# OpenOTA.net
KiCad netlist of a schematic drawn in EAGLE
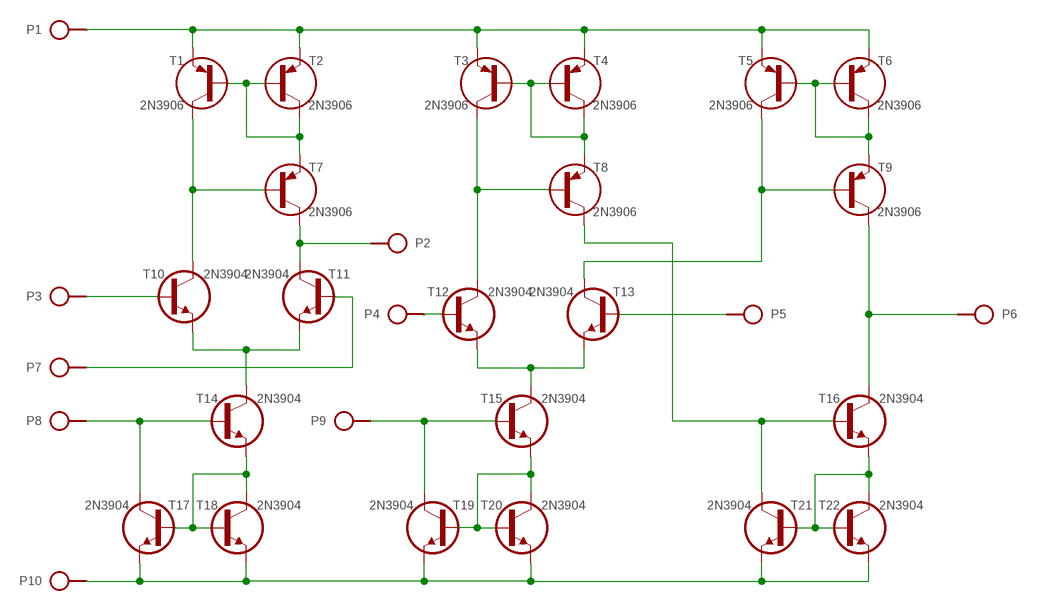
[diagram p0: schematic, sheet 1]

(export (version "E")
  (design (tool "Eeschema 10.0.6"))
  (components
    (comp (ref "P1")
      (value "SPAD")
      (footprint "eagle-import:SPAD")
      (libsource (lib "eagle-import") (part "SPAD"))
    )
    (comp (ref "P2")
      (value "SPAD")
      (footprint "eagle-import:SPAD")
      (libsource (lib "eagle-import") (part "SPAD"))
    )
    (comp (ref "P3")
      (value "SPAD")
      (footprint "eagle-import:SPAD")
      (libsource (lib "eagle-import") (part "SPAD"))
    )
    (comp (ref "P4")
      (value "SPAD")
      (footprint "eagle-import:SPAD")
      (libsource (lib "eagle-import") (part "SPAD"))
    )
    (comp (ref "P5")
      (value "SPAD")
      (footprint "eagle-import:SPAD")
      (libsource (lib "eagle-import") (part "SPAD"))
    )
    (comp (ref "P6")
      (value "SPAD")
      (footprint "eagle-import:SPAD")
      (libsource (lib "eagle-import") (part "SPAD"))
    )
    (comp (ref "P7")
      (value "SPAD")
      (footprint "eagle-import:SPAD")
      (libsource (lib "eagle-import") (part "SPAD"))
    )
    (comp (ref "P8")
      (value "SPAD")
      (footprint "eagle-import:SPAD")
      (libsource (lib "eagle-import") (part "SPAD"))
    )
    (comp (ref "P9")
      (value "SPAD")
      (footprint "eagle-import:SPAD")
      (libsource (lib "eagle-import") (part "SPAD"))
    )
    (comp (ref "P10")
      (value "SPAD")
      (footprint "eagle-import:SPAD")
      (libsource (lib "eagle-import") (part "SPAD"))
    )
    (comp (ref "T1")
      (value "2N3906")
      (footprint "eagle-import:TO92")
      (libsource (lib "eagle-import") (part "2N3906"))
    )
    (comp (ref "T2")
      (value "2N3906")
      (footprint "eagle-import:TO92")
      (libsource (lib "eagle-import") (part "2N3906"))
    )
    (comp (ref "T3")
      (value "2N3906")
      (footprint "eagle-import:TO92")
      (libsource (lib "eagle-import") (part "2N3906"))
    )
    (comp (ref "T4")
      (value "2N3906")
      (footprint "eagle-import:TO92")
      (libsource (lib "eagle-import") (part "2N3906"))
    )
    (comp (ref "T5")
      (value "2N3906")
      (footprint "eagle-import:TO92")
      (libsource (lib "eagle-import") (part "2N3906"))
    )
    (comp (ref "T6")
      (value "2N3906")
      (footprint "eagle-import:TO92")
      (libsource (lib "eagle-import") (part "2N3906"))
    )
    (comp (ref "T7")
      (value "2N3906")
      (footprint "eagle-import:TO92")
      (libsource (lib "eagle-import") (part "2N3906"))
    )
    (comp (ref "T8")
      (value "2N3906")
      (footprint "eagle-import:TO92")
      (libsource (lib "eagle-import") (part "2N3906"))
    )
    (comp (ref "T9")
      (value "2N3906")
      (footprint "eagle-import:TO92")
      (libsource (lib "eagle-import") (part "2N3906"))
    )
    (comp (ref "T10")
      (value "2N3904")
      (footprint "eagle-import:TO92")
      (libsource (lib "eagle-import") (part "2N3904"))
    )
    (comp (ref "T11")
      (value "2N3904")
      (footprint "eagle-import:TO92")
      (libsource (lib "eagle-import") (part "2N3904"))
    )
    (comp (ref "T12")
      (value "2N3904")
      (footprint "eagle-import:TO92")
      (libsource (lib "eagle-import") (part "2N3904"))
    )
    (comp (ref "T13")
      (value "2N3904")
      (footprint "eagle-import:TO92")
      (libsource (lib "eagle-import") (part "2N3904"))
    )
    (comp (ref "T14")
      (value "2N3904")
      (footprint "eagle-import:TO92")
      (libsource (lib "eagle-import") (part "2N3904"))
    )
    (comp (ref "T15")
      (value "2N3904")
      (footprint "eagle-import:TO92")
      (libsource (lib "eagle-import") (part "2N3904"))
    )
    (comp (ref "T16")
      (value "2N3904")
      (footprint "eagle-import:TO92")
      (libsource (lib "eagle-import") (part "2N3904"))
    )
    (comp (ref "T17")
      (value "2N3904")
      (footprint "eagle-import:TO92")
      (libsource (lib "eagle-import") (part "2N3904"))
    )
    (comp (ref "T18")
      (value "2N3904")
      (footprint "eagle-import:TO92")
      (libsource (lib "eagle-import") (part "2N3904"))
    )
    (comp (ref "T19")
      (value "2N3904")
      (footprint "eagle-import:TO92")
      (libsource (lib "eagle-import") (part "2N3904"))
    )
    (comp (ref "T20")
      (value "2N3904")
      (footprint "eagle-import:TO92")
      (libsource (lib "eagle-import") (part "2N3904"))
    )
    (comp (ref "T21")
      (value "2N3904")
      (footprint "eagle-import:TO92")
      (libsource (lib "eagle-import") (part "2N3904"))
    )
    (comp (ref "T22")
      (value "2N3904")
      (footprint "eagle-import:TO92")
      (libsource (lib "eagle-import") (part "2N3904"))
    )
  )
  (nets
    (net (code "1") (name "Net-(P1-P$1)") (class "Default")
      (node (ref "P1") (pin "1") (pinfunction "P$1_1") (pintype "passive"))
      (node (ref "T1") (pin "1") (pinfunction "E_1") (pintype "passive"))
      (node (ref "T2") (pin "1") (pinfunction "E_1") (pintype "passive"))
      (node (ref "T3") (pin "1") (pinfunction "E_1") (pintype "passive"))
      (node (ref "T4") (pin "1") (pinfunction "E_1") (pintype "passive"))
      (node (ref "T5") (pin "1") (pinfunction "E_1") (pintype "passive"))
      (node (ref "T6") (pin "1") (pinfunction "E_1") (pintype "passive"))
    )
    (net (code "2") (name "Net-(P2-P$1)") (class "Default")
      (node (ref "P2") (pin "1") (pinfunction "P$1_1") (pintype "passive"))
      (node (ref "T11") (pin "3") (pinfunction "C_3") (pintype "passive"))
      (node (ref "T7") (pin "3") (pinfunction "C_3") (pintype "passive"))
    )
    (net (code "3") (name "Net-(P3-P$1)") (class "Default")
      (node (ref "P3") (pin "1") (pinfunction "P$1_1") (pintype "passive"))
      (node (ref "T10") (pin "2") (pinfunction "B_2") (pintype "passive"))
    )
    (net (code "4") (name "Net-(P4-P$1)") (class "Default")
      (node (ref "P4") (pin "1") (pinfunction "P$1_1") (pintype "passive"))
      (node (ref "T12") (pin "2") (pinfunction "B_2") (pintype "passive"))
    )
    (net (code "5") (name "Net-(P5-P$1)") (class "Default")
      (node (ref "P5") (pin "1") (pinfunction "P$1_1") (pintype "passive"))
      (node (ref "T13") (pin "2") (pinfunction "B_2") (pintype "passive"))
    )
    (net (code "6") (name "Net-(P6-P$1)") (class "Default")
      (node (ref "P6") (pin "1") (pinfunction "P$1_1") (pintype "passive"))
      (node (ref "T16") (pin "3") (pinfunction "C_3") (pintype "passive"))
      (node (ref "T9") (pin "3") (pinfunction "C_3") (pintype "passive"))
    )
    (net (code "7") (name "Net-(P7-P$1)") (class "Default")
      (node (ref "P7") (pin "1") (pinfunction "P$1_1") (pintype "passive"))
      (node (ref "T11") (pin "2") (pinfunction "B_2") (pintype "passive"))
    )
    (net (code "8") (name "Net-(P8-P$1)") (class "Default")
      (node (ref "P8") (pin "1") (pinfunction "P$1_1") (pintype "passive"))
      (node (ref "T14") (pin "2") (pinfunction "B_2") (pintype "passive"))
      (node (ref "T17") (pin "3") (pinfunction "C_3") (pintype "passive"))
    )
    (net (code "9") (name "Net-(P9-P$1)") (class "Default")
      (node (ref "P9") (pin "1") (pinfunction "P$1_1") (pintype "passive"))
      (node (ref "T15") (pin "2") (pinfunction "B_2") (pintype "passive"))
      (node (ref "T19") (pin "3") (pinfunction "C_3") (pintype "passive"))
    )
    (net (code "10") (name "Net-(P10-P$1)") (class "Default")
      (node (ref "P10") (pin "1") (pinfunction "P$1_1") (pintype "passive"))
      (node (ref "T17") (pin "1") (pinfunction "E_1") (pintype "passive"))
      (node (ref "T18") (pin "1") (pinfunction "E_1") (pintype "passive"))
      (node (ref "T19") (pin "1") (pinfunction "E_1") (pintype "passive"))
      (node (ref "T20") (pin "1") (pinfunction "E_1") (pintype "passive"))
      (node (ref "T21") (pin "1") (pinfunction "E_1") (pintype "passive"))
      (node (ref "T22") (pin "1") (pinfunction "E_1") (pintype "passive"))
    )
    (net (code "11") (name "Net-(T1-B)") (class "Default")
      (node (ref "T1") (pin "2") (pinfunction "B_2") (pintype "passive"))
      (node (ref "T2") (pin "2") (pinfunction "B_2") (pintype "passive"))
      (node (ref "T2") (pin "3") (pinfunction "C_3") (pintype "passive"))
      (node (ref "T7") (pin "1") (pinfunction "E_1") (pintype "passive"))
    )
    (net (code "12") (name "Net-(T1-C)") (class "Default")
      (node (ref "T1") (pin "3") (pinfunction "C_3") (pintype "passive"))
      (node (ref "T10") (pin "3") (pinfunction "C_3") (pintype "passive"))
      (node (ref "T7") (pin "2") (pinfunction "B_2") (pintype "passive"))
    )
    (net (code "13") (name "Net-(T3-B)") (class "Default")
      (node (ref "T3") (pin "2") (pinfunction "B_2") (pintype "passive"))
      (node (ref "T4") (pin "2") (pinfunction "B_2") (pintype "passive"))
      (node (ref "T4") (pin "3") (pinfunction "C_3") (pintype "passive"))
      (node (ref "T8") (pin "1") (pinfunction "E_1") (pintype "passive"))
    )
    (net (code "14") (name "Net-(T5-B)") (class "Default")
      (node (ref "T5") (pin "2") (pinfunction "B_2") (pintype "passive"))
      (node (ref "T6") (pin "2") (pinfunction "B_2") (pintype "passive"))
      (node (ref "T6") (pin "3") (pinfunction "C_3") (pintype "passive"))
      (node (ref "T9") (pin "1") (pinfunction "E_1") (pintype "passive"))
    )
    (net (code "15") (name "Net-(T10-E)") (class "Default")
      (node (ref "T10") (pin "1") (pinfunction "E_1") (pintype "passive"))
      (node (ref "T11") (pin "1") (pinfunction "E_1") (pintype "passive"))
      (node (ref "T14") (pin "3") (pinfunction "C_3") (pintype "passive"))
    )
    (net (code "16") (name "Net-(T12-C)") (class "Default")
      (node (ref "T12") (pin "3") (pinfunction "C_3") (pintype "passive"))
      (node (ref "T3") (pin "3") (pinfunction "C_3") (pintype "passive"))
      (node (ref "T8") (pin "2") (pinfunction "B_2") (pintype "passive"))
    )
    (net (code "17") (name "Net-(T12-E)") (class "Default")
      (node (ref "T12") (pin "1") (pinfunction "E_1") (pintype "passive"))
      (node (ref "T13") (pin "1") (pinfunction "E_1") (pintype "passive"))
      (node (ref "T15") (pin "3") (pinfunction "C_3") (pintype "passive"))
    )
    (net (code "18") (name "Net-(T13-C)") (class "Default")
      (node (ref "T13") (pin "3") (pinfunction "C_3") (pintype "passive"))
      (node (ref "T5") (pin "3") (pinfunction "C_3") (pintype "passive"))
      (node (ref "T9") (pin "2") (pinfunction "B_2") (pintype "passive"))
    )
    (net (code "19") (name "Net-(T14-E)") (class "Default")
      (node (ref "T14") (pin "1") (pinfunction "E_1") (pintype "passive"))
      (node (ref "T17") (pin "2") (pinfunction "B_2") (pintype "passive"))
      (node (ref "T18") (pin "2") (pinfunction "B_2") (pintype "passive"))
      (node (ref "T18") (pin "3") (pinfunction "C_3") (pintype "passive"))
    )
    (net (code "20") (name "Net-(T15-E)") (class "Default")
      (node (ref "T15") (pin "1") (pinfunction "E_1") (pintype "passive"))
      (node (ref "T19") (pin "2") (pinfunction "B_2") (pintype "passive"))
      (node (ref "T20") (pin "2") (pinfunction "B_2") (pintype "passive"))
      (node (ref "T20") (pin "3") (pinfunction "C_3") (pintype "passive"))
    )
    (net (code "21") (name "Net-(T16-B)") (class "Default")
      (node (ref "T16") (pin "2") (pinfunction "B_2") (pintype "passive"))
      (node (ref "T21") (pin "3") (pinfunction "C_3") (pintype "passive"))
      (node (ref "T8") (pin "3") (pinfunction "C_3") (pintype "passive"))
    )
    (net (code "22") (name "Net-(T16-E)") (class "Default")
      (node (ref "T16") (pin "1") (pinfunction "E_1") (pintype "passive"))
      (node (ref "T21") (pin "2") (pinfunction "B_2") (pintype "passive"))
      (node (ref "T22") (pin "2") (pinfunction "B_2") (pintype "passive"))
      (node (ref "T22") (pin "3") (pinfunction "C_3") (pintype "passive"))
    )
  )
)
